# sensor.net
KiCad netlist of a schematic drawn in Altium Designer
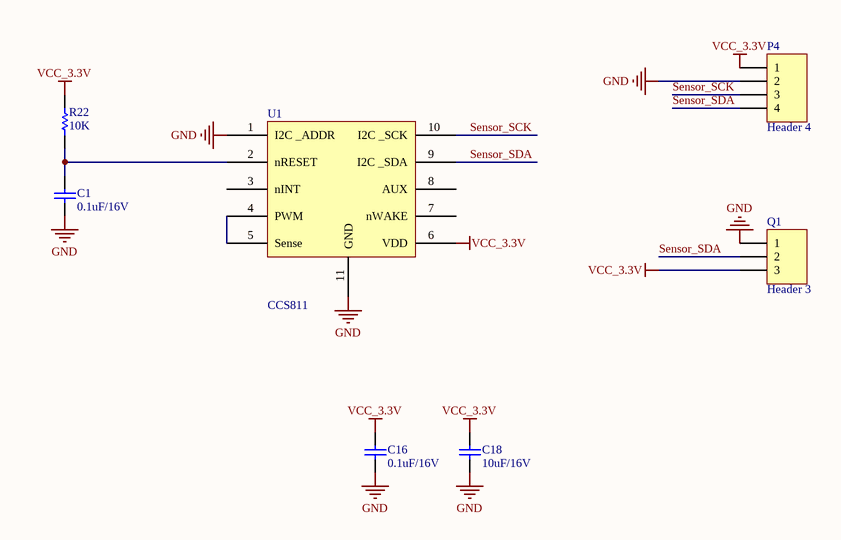
[diagram p0: sensor.SchDoc]

(export (version "E")
  (design (tool "Eeschema 10.0.6"))
  (components
    (comp (ref "C1")
      (value "0.1uF/16V")
      (footprint "0603C")
      (description "Capacitor")
      (fields (field (name "PUBLISHER") "Altium Limited"))
      (libsource (lib "Miscellaneous Devices") (part "Cap"))
    )
    (comp (ref "C16")
      (value "0.1uF/16V")
      (footprint "0603C")
      (description "Capacitor")
      (fields (field (name "PUBLISHER") "Altium Limited"))
      (libsource (lib "Miscellaneous Devices") (part "Cap"))
    )
    (comp (ref "C18")
      (value "10uF/16V")
      (footprint "0603C")
      (description "Capacitor")
      (fields (field (name "PUBLISHER") "Altium Limited"))
      (libsource (lib "Miscellaneous Devices") (part "Cap"))
    )
    (comp (ref "P4")
      (value "Header 4")
      (footprint "Pcblib_20110825:4-2.5MM-W")
      (description "Header, 4-Pin")
      (fields (field (name "PUBLISHER") "Altium Limited"))
      (libsource (lib "Miscellaneous Connectors") (part "Header 4"))
    )
    (comp (ref "Q1")
      (value "Header 3")
      (footprint "TO-92")
      (description "Header, 3-Pin")
      (fields (field (name "PUBLISHER") "Altium Limited"))
      (libsource (lib "Miscellaneous Connectors") (part "Header 3"))
    )
    (comp (ref "R22")
      (value "10K")
      (footprint "0603R")
      (description "Resistor")
      (fields (field (name "PUBLISHER") "Altium Limited"))
      (libsource (lib "Miscellaneous Devices") (part "Res1"))
    )
    (comp (ref "U1")
      (value "CCS811")
      (footprint "Pcblib_20110825:QFN60P270X400X80-10N")
      (libsource (lib "stm32") (part "CCS811"))
    )
  )
  (nets
    (net (code "1") (name "/Sensor_SCK") (class "Default")
      (node (ref "P4") (pin "3") (pinfunction "3_3") (pintype "passive"))
      (node (ref "U1") (pin "10") (pinfunction "I2C__SCK_10") (pintype "passive"))
    )
    (net (code "2") (name "/Sensor_SDA") (class "Default")
      (node (ref "P4") (pin "4") (pinfunction "4_4") (pintype "passive"))
      (node (ref "Q1") (pin "2") (pinfunction "2_2") (pintype "passive"))
      (node (ref "U1") (pin "9") (pinfunction "I2C__SDA_9") (pintype "passive"))
    )
    (net (code "3") (name "GND") (class "Default")
      (node (ref "C1") (pin "2") (pinfunction "2_2") (pintype "passive"))
      (node (ref "C16") (pin "2") (pinfunction "2_2") (pintype "passive"))
      (node (ref "C18") (pin "2") (pinfunction "2_2") (pintype "passive"))
      (node (ref "P4") (pin "2") (pinfunction "2_2") (pintype "passive"))
      (node (ref "Q1") (pin "1") (pinfunction "1_1") (pintype "passive"))
      (node (ref "U1") (pin "1") (pinfunction "I2C__ADDR_1") (pintype "passive"))
      (node (ref "U1") (pin "11") (pinfunction "GND_11") (pintype "passive"))
    )
    (net (code "4") (name "Net-(U1-PWM)") (class "Default")
      (node (ref "U1") (pin "4") (pinfunction "PWM_4") (pintype "passive"))
      (node (ref "U1") (pin "5") (pinfunction "Sense_5") (pintype "passive"))
    )
    (net (code "5") (name "Net-(U1-nRESET)") (class "Default")
      (node (ref "C1") (pin "1") (pinfunction "1_1") (pintype "passive"))
      (node (ref "R22") (pin "1") (pinfunction "1_1") (pintype "passive"))
      (node (ref "U1") (pin "2") (pinfunction "nRESET_2") (pintype "passive"))
    )
    (net (code "6") (name "VCC_3.3V") (class "Default")
      (node (ref "C16") (pin "1") (pinfunction "1_1") (pintype "passive"))
      (node (ref "C18") (pin "1") (pinfunction "1_1") (pintype "passive"))
      (node (ref "P4") (pin "1") (pinfunction "1_1") (pintype "passive"))
      (node (ref "Q1") (pin "3") (pinfunction "3_3") (pintype "passive"))
      (node (ref "R22") (pin "2") (pinfunction "2_2") (pintype "passive"))
      (node (ref "U1") (pin "6") (pinfunction "VDD_6") (pintype "passive"))
    )
    (net (code "7") (name "unconnected-(U1-AUX-Pad8)") (class "Default")
      (node (ref "U1") (pin "8") (pinfunction "AUX_8") (pintype "passive"))
    )
    (net (code "8") (name "unconnected-(U1-nINT-Pad3)") (class "Default")
      (node (ref "U1") (pin "3") (pinfunction "nINT_3") (pintype "passive"))
    )
    (net (code "9") (name "unconnected-(U1-nWAKE-Pad7)") (class "Default")
      (node (ref "U1") (pin "7") (pinfunction "nWAKE_7") (pintype "passive"))
    )
  )
)
